# 06_FLASH.net
KiCad netlist of a schematic drawn in Altium Designer
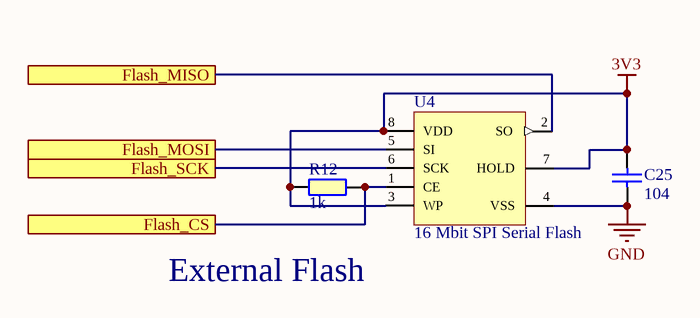
[diagram p0: [06].FLASH.SchDoc]

(export (version "E")
  (design (tool "Eeschema 10.0.6"))
  (components
    (comp (ref "C25")
      (value "104")
      (footprint "C_0603")
      (description "Capacitor SMD")
      (fields (field (name "PUBLISHER") "Altium Limited"))
      (libsource (lib "ThanhNT") (part "Cap SMD 0805"))
    )
    (comp (ref "R12") (value "1k") (footprint "R_0603") (libsource (lib "DungMV") (part "RES_0805")))
    (comp (ref "U4")
      (value "16 Mbit SPI Serial Flash")
      (footprint "SST25")
      (fields (field (name "MPN") "SST25VF016B-50-4I-S2AF"))
      (libsource (lib "ThanhNT") (part "SST25VF016B"))
    )
  )
  (nets
    (net (code "1") (name "/Flash_CS") (class "Default")
      (node (ref "R12") (pin "2") (pinfunction "2_2") (pintype "passive"))
      (node (ref "U4") (pin "1") (pinfunction "CE_1") (pintype "passive"))
    )
    (net (code "2") (name "/Flash_MISO") (class "Default")
      (node (ref "U4") (pin "2") (pinfunction "SO_2") (pintype "output"))
    )
    (net (code "3") (name "/Flash_MOSI") (class "Default")
      (node (ref "U4") (pin "5") (pinfunction "SI_5") (pintype "passive"))
    )
    (net (code "4") (name "/Flash_SCK") (class "Default")
      (node (ref "U4") (pin "6") (pinfunction "SCK_6") (pintype "passive"))
    )
    (net (code "5") (name "3V3") (class "Default")
      (node (ref "C25") (pin "2") (pinfunction "2_2") (pintype "passive"))
      (node (ref "R12") (pin "1") (pinfunction "1_1") (pintype "passive"))
      (node (ref "U4") (pin "3") (pinfunction "WP_3") (pintype "passive"))
      (node (ref "U4") (pin "7") (pinfunction "HOLD_7") (pintype "passive"))
      (node (ref "U4") (pin "8") (pinfunction "VDD_8") (pintype "power_in"))
    )
    (net (code "6") (name "GND") (class "Default")
      (node (ref "C25") (pin "1") (pinfunction "1_1") (pintype "passive"))
      (node (ref "U4") (pin "4") (pinfunction "VSS_4") (pintype "passive"))
    )
  )
)
